# PWM_Soldeerbout.net
KiCad netlist of a schematic drawn in Altium Designer
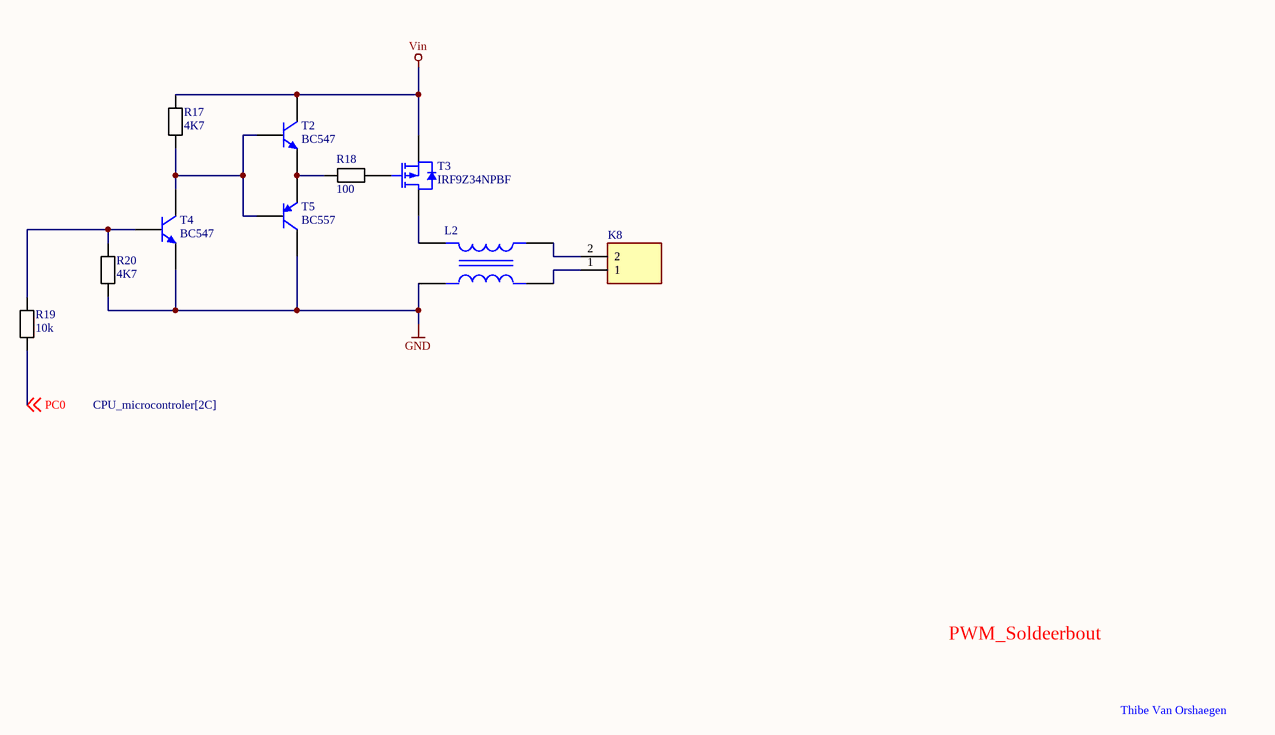
[diagram p0: PWM_Soldeerbout.schdoc]

(export (version "E")
  (design (tool "Eeschema 10.0.6"))
  (components
    (comp (ref "K8")
      (value "~")
      (footprint "PcbLib3:Schroefconnector 2 Pin")
      (description "Connector")
      (fields (field (name "MANUFACTURER_PART_NUMBER") "282836-2"))
      (libsource (lib "Soldeerstation") (part "Schroefconnector 2 Pin L"))
    )
    (comp (ref "L2")
      (value "~")
      (footprint "2545")
      (libsource (lib "Soldeerstation") (part "Common_Mode_Choke"))
    )
    (comp (ref "R17")
      (value "4K7")
      (footprint "RESC2013X50X30ML20T20")
      (fields (field (name "MANUFACTURER") "Vishay Dale") (field (name "PART NUMBER") "CRCW08050000Z0EA"))
      (libsource (lib "Soldeerstation") (part "Weerstand"))
    )
    (comp (ref "R18")
      (value "100")
      (footprint "RESC2013X50X30ML20T20")
      (fields (field (name "MANUFACTURER") "Vishay Dale") (field (name "PART NUMBER") "CRCW08050000Z0EA"))
      (libsource (lib "Soldeerstation") (part "Weerstand"))
    )
    (comp (ref "R19")
      (value "10k")
      (footprint "RESC2013X50X30ML20T20")
      (fields (field (name "MANUFACTURER") "Vishay Dale") (field (name "PART NUMBER") "CRCW08050000Z0EA"))
      (libsource (lib "Soldeerstation") (part "Weerstand"))
    )
    (comp (ref "R20")
      (value "4K7")
      (footprint "RESC2013X50X30ML20T20")
      (fields (field (name "MANUFACTURER") "Vishay Dale") (field (name "PART NUMBER") "CRCW08050000Z0EA"))
      (libsource (lib "Soldeerstation") (part "Weerstand"))
    )
    (comp (ref "T2")
      (value "BC547")
      (footprint "SOT_23")
      (fields (field (name "MANUFACTURER") "On Semiconductor") (field (name "PARTNUMBER") "BC547C"))
      (libsource (lib "Soldeerstation") (part "Transistor_NPN"))
    )
    (comp (ref "T3")
      (value "IRF9Z34NPBF")
      (footprint "TO_252")
      (fields (field (name "MANUFACTURER") "Fairchild Semiconductor"))
      (libsource (lib "Soldeerstation") (part "MOSFET_P"))
    )
    (comp (ref "T4")
      (value "BC547")
      (footprint "SOT_23")
      (fields (field (name "MANUFACTURER") "On Semiconductor") (field (name "PARTNUMBER") "BC547C"))
      (libsource (lib "Soldeerstation") (part "Transistor_NPN"))
    )
    (comp (ref "T5")
      (value "BC557")
      (footprint "SOT_23")
      (fields (field (name "MANUFACTURER") "On Semiconductor") (field (name "PARTNUMBER") "BC557C"))
      (libsource (lib "Soldeerstation") (part "Transistor_PNP"))
    )
  )
  (nets
    (net (code "1") (name "GND") (class "Default")
      (node (ref "L2") (pin "2") (pinfunction "2_2") (pintype "passive"))
      (node (ref "R20") (pin "1") (pinfunction "1_1") (pintype "passive"))
      (node (ref "T4") (pin "3") (pinfunction "E_3") (pintype "passive"))
      (node (ref "T5") (pin "1") (pinfunction "C_1") (pintype "passive"))
    )
    (net (code "2") (name "Net-(K8-Pad1)") (class "Default")
      (node (ref "K8") (pin "1") (pinfunction "1_1") (pintype "passive"))
      (node (ref "L2") (pin "3") (pinfunction "3_3") (pintype "passive"))
    )
    (net (code "3") (name "Net-(K8-Pad2)") (class "Default")
      (node (ref "K8") (pin "2") (pinfunction "2_2") (pintype "passive"))
      (node (ref "L2") (pin "4") (pinfunction "4_4") (pintype "passive"))
    )
    (net (code "4") (name "Net-(T2-B)") (class "Default")
      (node (ref "R17") (pin "1") (pinfunction "1_1") (pintype "passive"))
      (node (ref "T2") (pin "2") (pinfunction "B_2") (pintype "passive"))
      (node (ref "T4") (pin "1") (pinfunction "C_1") (pintype "passive"))
      (node (ref "T5") (pin "2") (pinfunction "B_2") (pintype "passive"))
    )
    (net (code "5") (name "Net-(T2-E)") (class "Default")
      (node (ref "R18") (pin "1") (pinfunction "1_1") (pintype "passive"))
      (node (ref "T2") (pin "3") (pinfunction "E_3") (pintype "passive"))
      (node (ref "T5") (pin "3") (pinfunction "E_3") (pintype "passive"))
    )
    (net (code "6") (name "Net-(T3-DRAIN)") (class "Default")
      (node (ref "L2") (pin "1") (pinfunction "1_1") (pintype "passive"))
      (node (ref "T3") (pin "3") (pinfunction "DRAIN_3") (pintype "passive"))
    )
    (net (code "7") (name "Net-(T4-B)") (class "Default")
      (node (ref "R19") (pin "2") (pinfunction "2_2") (pintype "passive"))
      (node (ref "R20") (pin "2") (pinfunction "2_2") (pintype "passive"))
      (node (ref "T4") (pin "2") (pinfunction "B_2") (pintype "passive"))
    )
    (net (code "8") (name "PC0") (class "Default")
      (node (ref "R19") (pin "1") (pinfunction "1_1") (pintype "passive"))
    )
    (net (code "9") (name "Vin") (class "Default")
      (node (ref "R17") (pin "2") (pinfunction "2_2") (pintype "passive"))
      (node (ref "T2") (pin "1") (pinfunction "C_1") (pintype "passive"))
      (node (ref "T3") (pin "2") (pinfunction "SOURCE_2") (pintype "passive"))
    )
    (net (code "10") (name "unconnected-(R18-Pad2)") (class "Default")
      (node (ref "R18") (pin "2") (pinfunction "2_2") (pintype "passive"))
    )
    (net (code "11") (name "unconnected-(T3-GATE-Pad1)") (class "Default")
      (node (ref "T3") (pin "1") (pinfunction "GATE_1") (pintype "passive"))
    )
  )
)
